# touch-tara-h.net
KiCad netlist of a schematic drawn in Altium Designer
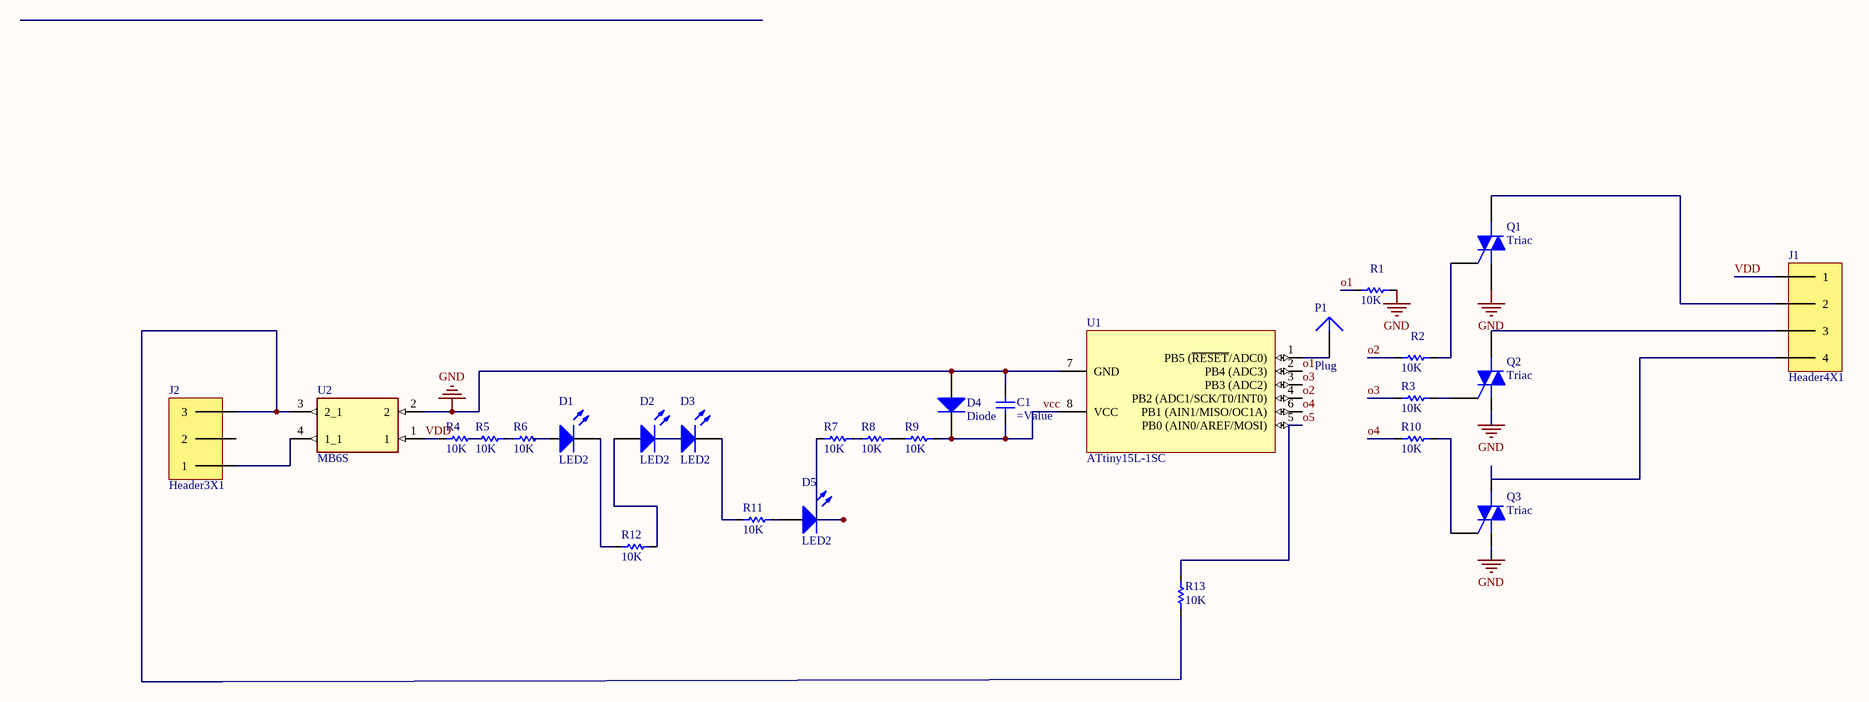
[diagram p0: touch-tara-h.SchDoc]

(export (version "E")
  (design (tool "Eeschema 10.0.6"))
  (components
    (comp (ref "C1")
      (value "~")
      (footprint "CAP 1206")
      (description "Capacitor")
      (libsource (lib "AltiumLib1") (part "Capacitor"))
    )
    (comp (ref "D1")
      (value "LED2")
      (footprint "3.2X1.6X1.1")
      (description "Typical RED, GREEN, YELLOW, AMBER GaAs LED")
      (fields (field (name "PUBLISHER") "Altium Limited"))
      (libsource (lib "Miscellaneous Devices") (part "LED2"))
    )
    (comp (ref "D2")
      (value "LED2")
      (footprint "3.2X1.6X1.1")
      (description "Typical RED, GREEN, YELLOW, AMBER GaAs LED")
      (fields (field (name "PUBLISHER") "Altium Limited"))
      (libsource (lib "Miscellaneous Devices") (part "LED2"))
    )
    (comp (ref "D3")
      (value "LED2")
      (footprint "3.2X1.6X1.1")
      (description "Typical RED, GREEN, YELLOW, AMBER GaAs LED")
      (fields (field (name "PUBLISHER") "Altium Limited"))
      (libsource (lib "Miscellaneous Devices") (part "LED2"))
    )
    (comp (ref "D4")
      (value "Diode")
      (footprint "C1206")
      (description "Default Diode")
      (fields (field (name "PUBLISHER") "Altium Limited"))
      (libsource (lib "Miscellaneous Devices") (part "Diode"))
    )
    (comp (ref "D5")
      (value "LED2")
      (footprint "3.2X1.6X1.1")
      (description "Typical RED, GREEN, YELLOW, AMBER GaAs LED")
      (fields (field (name "PUBLISHER") "Altium Limited"))
      (libsource (lib "Miscellaneous Devices") (part "LED2"))
    )
    (comp (ref "J1")
      (value "Header4X1")
      (footprint "HEADER 4X1")
      (libsource (lib "AltiumLib1") (part "Header4X1"))
    )
    (comp (ref "J2")
      (value "Header3X1")
      (footprint "HEADER 3X1")
      (libsource (lib "AltiumLib1") (part "Header3X1"))
    )
    (comp (ref "P1")
      (value "Plug")
      (footprint "PIN1")
      (fields (field (name "PUBLISHER") "Altium Limited"))
      (libsource (lib "Miscellaneous Connectors") (part "Plug"))
    )
    (comp (ref "Q1")
      (value "Triac")
      (footprint "SOT89N")
      (description "Silicon Bidirectional Triode Thyristor")
      (fields (field (name "PUBLISHER") "Altium Limited"))
      (libsource (lib "Miscellaneous Devices") (part "Triac"))
    )
    (comp (ref "Q2")
      (value "Triac")
      (footprint "SOT89N")
      (description "Silicon Bidirectional Triode Thyristor")
      (fields (field (name "PUBLISHER") "Altium Limited"))
      (libsource (lib "Miscellaneous Devices") (part "Triac"))
    )
    (comp (ref "Q3")
      (value "Triac")
      (footprint "SOT89N")
      (description "Silicon Bidirectional Triode Thyristor")
      (fields (field (name "PUBLISHER") "Altium Limited"))
      (libsource (lib "Miscellaneous Devices") (part "Triac"))
    )
    (comp (ref "R1")
      (value "10K")
      (footprint "RES 1206 (3216X08L)")
      (description "Resistor")
      (fields (field (name "TOLERANCE") "5%") (field (name "POWER") "1/4 W"))
      (libsource (lib "AltiumLib1") (part "Resistor"))
    )
    (comp (ref "R2")
      (value "10K")
      (footprint "RES 1206 (3216X08L)")
      (description "Resistor")
      (fields (field (name "TOLERANCE") "5%") (field (name "POWER") "1/4 W"))
      (libsource (lib "AltiumLib1") (part "Resistor"))
    )
    (comp (ref "R3")
      (value "10K")
      (footprint "RES 1206 (3216X08L)")
      (description "Resistor")
      (fields (field (name "TOLERANCE") "5%") (field (name "POWER") "1/4 W"))
      (libsource (lib "AltiumLib1") (part "Resistor"))
    )
    (comp (ref "R4")
      (value "10K")
      (footprint "RES 2010 (5026X08L)")
      (description "Resistor")
      (fields (field (name "TOLERANCE") "5%") (field (name "POWER") "1/4 W"))
      (libsource (lib "AltiumLib1") (part "Resistor"))
    )
    (comp (ref "R5")
      (value "10K")
      (footprint "RES 2010 (5026X08L)")
      (description "Resistor")
      (fields (field (name "TOLERANCE") "5%") (field (name "POWER") "1/4 W"))
      (libsource (lib "AltiumLib1") (part "Resistor"))
    )
    (comp (ref "R6")
      (value "10K")
      (footprint "RES 2010 (5026X08L)")
      (description "Resistor")
      (fields (field (name "TOLERANCE") "5%") (field (name "POWER") "1/4 W"))
      (libsource (lib "AltiumLib1") (part "Resistor"))
    )
    (comp (ref "R7")
      (value "10K")
      (footprint "RES 2010 (5026X08L)")
      (description "Resistor")
      (fields (field (name "TOLERANCE") "5%") (field (name "POWER") "1/4 W"))
      (libsource (lib "AltiumLib1") (part "Resistor"))
    )
    (comp (ref "R8")
      (value "10K")
      (footprint "RES 2010 (5026X08L)")
      (description "Resistor")
      (fields (field (name "TOLERANCE") "5%") (field (name "POWER") "1/4 W"))
      (libsource (lib "AltiumLib1") (part "Resistor"))
    )
    (comp (ref "R9")
      (value "10K")
      (footprint "RES 2010 (5026X08L)")
      (description "Resistor")
      (fields (field (name "TOLERANCE") "5%") (field (name "POWER") "1/4 W"))
      (libsource (lib "AltiumLib1") (part "Resistor"))
    )
    (comp (ref "R10")
      (value "10K")
      (footprint "RES 1206 (3216X08L)")
      (description "Resistor")
      (fields (field (name "TOLERANCE") "5%") (field (name "POWER") "1/4 W"))
      (libsource (lib "AltiumLib1") (part "Resistor"))
    )
    (comp (ref "R11")
      (value "10K")
      (footprint "RES 2010 (5026X08L)")
      (description "Resistor")
      (fields (field (name "TOLERANCE") "5%") (field (name "POWER") "1/4 W"))
      (libsource (lib "AltiumLib1") (part "Resistor"))
    )
    (comp (ref "R12")
      (value "10K")
      (footprint "RES 2010 (5026X08L)")
      (description "Resistor")
      (fields (field (name "TOLERANCE") "5%") (field (name "POWER") "1/4 W"))
      (libsource (lib "AltiumLib1") (part "Resistor"))
    )
    (comp (ref "R13")
      (value "10K")
      (footprint "RES 1206 (3216X08L)")
      (description "Resistor")
      (fields (field (name "TOLERANCE") "5%") (field (name "POWER") "1/4 W"))
      (libsource (lib "AltiumLib1") (part "Resistor"))
    )
    (comp (ref "U1")
      (value "ATtiny15L-1SC")
      (footprint "8S2_N")
      (description "8-Bit AVR Microcontroller with 1K Byte of Flash Memory")
      (fields (field (name "PUBLISHER") "Altium Limited"))
      (libsource (lib "Atmel Microcontroller 8-Bit AVR") (part "ATtiny15L-1SC"))
    )
    (comp (ref "U2")
      (value "MB6S")
      (footprint "SOIC245P670X270-4N")
      (description "Bridge Rectifier Single Phase Standard 600V Surface Mount 4-SOIC")
      (fields (field (name "MF") "ON Semiconductor") (field (name "DIGI-KEY_PART_NUMBER") "MB6SCT-ND"))
      (libsource (lib "MB6S") (part "MB6S"))
    )
  )
  (nets
    (net (code "1") (name "/VDD") (class "Default")
      (node (ref "J1") (pin "1") (pinfunction "1_1") (pintype "passive"))
      (node (ref "R4") (pin "1") (pinfunction "1_1") (pintype "passive"))
      (node (ref "U2") (pin "1") (pinfunction "1_1") (pintype "input"))
    )
    (net (code "2") (name "/o1") (class "Default")
      (node (ref "R1") (pin "1") (pinfunction "1_1") (pintype "passive"))
      (node (ref "U1") (pin "2") (pinfunction "PB4_(ADC3)_2") (pintype "bidirectional"))
    )
    (net (code "3") (name "/o2") (class "Default")
      (node (ref "R2") (pin "1") (pinfunction "1_1") (pintype "passive"))
      (node (ref "U1") (pin "4") (pinfunction "PB2_(ADC1/SCK/T0/INT0)_4") (pintype "bidirectional"))
    )
    (net (code "4") (name "/o3") (class "Default")
      (node (ref "R3") (pin "1") (pinfunction "1_1") (pintype "passive"))
      (node (ref "U1") (pin "3") (pinfunction "PB3_(ADC2)_3") (pintype "bidirectional"))
    )
    (net (code "5") (name "/o4") (class "Default")
      (node (ref "R10") (pin "1") (pinfunction "1_1") (pintype "passive"))
      (node (ref "U1") (pin "6") (pinfunction "PB1_(AIN1/MISO/OC1A)_6") (pintype "bidirectional"))
    )
    (net (code "6") (name "/o5") (class "Default")
      (node (ref "R13") (pin "2") (pinfunction "2_2") (pintype "passive"))
      (node (ref "U1") (pin "5") (pinfunction "PB0_(AIN0/AREF/MOSI)_5") (pintype "bidirectional"))
    )
    (net (code "7") (name "/vcc") (class "Default")
      (node (ref "C1") (pin "1") (pinfunction "+_1") (pintype "passive"))
      (node (ref "D4") (pin "2") (pinfunction "K_2") (pintype "passive"))
      (node (ref "R9") (pin "2") (pinfunction "2_2") (pintype "passive"))
      (node (ref "U1") (pin "8") (pinfunction "VCC_8") (pintype "power_in"))
    )
    (net (code "8") (name "GND") (class "Default")
      (node (ref "C1") (pin "2") (pinfunction "-_2") (pintype "passive"))
      (node (ref "D4") (pin "1") (pinfunction "A_1") (pintype "passive"))
      (node (ref "Q1") (pin "1") (pinfunction "M1_1") (pintype "passive"))
      (node (ref "Q2") (pin "1") (pinfunction "M1_1") (pintype "passive"))
      (node (ref "Q3") (pin "1") (pinfunction "M1_1") (pintype "passive"))
      (node (ref "R1") (pin "2") (pinfunction "2_2") (pintype "passive"))
      (node (ref "U1") (pin "7") (pinfunction "GND_7") (pintype "power_in"))
      (node (ref "U2") (pin "2") (pinfunction "2_2") (pintype "input"))
    )
    (net (code "9") (name "Net-(D1-A)") (class "Default")
      (node (ref "D1") (pin "1") (pinfunction "A_1") (pintype "passive"))
      (node (ref "R6") (pin "2") (pinfunction "2_2") (pintype "passive"))
    )
    (net (code "10") (name "Net-(D1-K)") (class "Default")
      (node (ref "D1") (pin "2") (pinfunction "K_2") (pintype "passive"))
      (node (ref "R12") (pin "1") (pinfunction "1_1") (pintype "passive"))
    )
    (net (code "11") (name "Net-(D2-A)") (class "Default")
      (node (ref "D2") (pin "1") (pinfunction "A_1") (pintype "passive"))
      (node (ref "R12") (pin "2") (pinfunction "2_2") (pintype "passive"))
    )
    (net (code "12") (name "Net-(D2-K)") (class "Default")
      (node (ref "D2") (pin "2") (pinfunction "K_2") (pintype "passive"))
      (node (ref "D3") (pin "1") (pinfunction "A_1") (pintype "passive"))
    )
    (net (code "13") (name "Net-(D3-K)") (class "Default")
      (node (ref "D3") (pin "2") (pinfunction "K_2") (pintype "passive"))
      (node (ref "R11") (pin "1") (pinfunction "1_1") (pintype "passive"))
    )
    (net (code "14") (name "Net-(D5-A)") (class "Default")
      (node (ref "D5") (pin "1") (pinfunction "A_1") (pintype "passive"))
      (node (ref "R11") (pin "2") (pinfunction "2_2") (pintype "passive"))
    )
    (net (code "15") (name "Net-(D5-K)") (class "Default")
      (node (ref "D5") (pin "2") (pinfunction "K_2") (pintype "passive"))
      (node (ref "R7") (pin "1") (pinfunction "1_1") (pintype "passive"))
    )
    (net (code "16") (name "Net-(Q1-G)") (class "Default")
      (node (ref "Q1") (pin "3") (pinfunction "G_3") (pintype "passive"))
      (node (ref "R2") (pin "2") (pinfunction "2_2") (pintype "passive"))
    )
    (net (code "17") (name "Net-(Q1-M2)") (class "Default")
      (node (ref "J1") (pin "2") (pinfunction "2_2") (pintype "passive"))
      (node (ref "Q1") (pin "2") (pinfunction "M2_2") (pintype "passive"))
    )
    (net (code "18") (name "Net-(Q2-G)") (class "Default")
      (node (ref "Q2") (pin "3") (pinfunction "G_3") (pintype "passive"))
      (node (ref "R3") (pin "2") (pinfunction "2_2") (pintype "passive"))
    )
    (net (code "19") (name "Net-(Q2-M2)") (class "Default")
      (node (ref "J1") (pin "3") (pinfunction "3_3") (pintype "passive"))
      (node (ref "Q2") (pin "2") (pinfunction "M2_2") (pintype "passive"))
    )
    (net (code "20") (name "Net-(Q3-G)") (class "Default")
      (node (ref "Q3") (pin "3") (pinfunction "G_3") (pintype "passive"))
      (node (ref "R10") (pin "2") (pinfunction "2_2") (pintype "passive"))
    )
    (net (code "21") (name "Net-(Q3-M2)") (class "Default")
      (node (ref "J1") (pin "4") (pinfunction "4_4") (pintype "passive"))
      (node (ref "Q3") (pin "2") (pinfunction "M2_2") (pintype "passive"))
    )
    (net (code "22") (name "Net-(R4-Pad2)") (class "Default")
      (node (ref "R4") (pin "2") (pinfunction "2_2") (pintype "passive"))
      (node (ref "R5") (pin "1") (pinfunction "1_1") (pintype "passive"))
    )
    (net (code "23") (name "Net-(R5-Pad2)") (class "Default")
      (node (ref "R5") (pin "2") (pinfunction "2_2") (pintype "passive"))
      (node (ref "R6") (pin "1") (pinfunction "1_1") (pintype "passive"))
    )
    (net (code "24") (name "Net-(R7-Pad2)") (class "Default")
      (node (ref "R7") (pin "2") (pinfunction "2_2") (pintype "passive"))
      (node (ref "R8") (pin "1") (pinfunction "1_1") (pintype "passive"))
    )
    (net (code "25") (name "Net-(R8-Pad2)") (class "Default")
      (node (ref "R8") (pin "2") (pinfunction "2_2") (pintype "passive"))
      (node (ref "R9") (pin "1") (pinfunction "1_1") (pintype "passive"))
    )
    (net (code "26") (name "Net-(U1-PB5_(~{RESET}{slash}ADC0))") (class "Default")
      (node (ref "P1") (pin "1") (pinfunction "1_1") (pintype "passive"))
      (node (ref "U1") (pin "1") (pinfunction "PB5_(~{RESET}/ADC0)_1") (pintype "bidirectional"))
    )
    (net (code "27") (name "Net-(U2-1_1)") (class "Default")
      (node (ref "J2") (pin "1") (pinfunction "1_1") (pintype "passive"))
      (node (ref "U2") (pin "4") (pinfunction "1_1_4") (pintype "output"))
    )
    (net (code "28") (name "Net-(U2-2_1)") (class "Default")
      (node (ref "J2") (pin "3") (pinfunction "3_3") (pintype "passive"))
      (node (ref "R13") (pin "1") (pinfunction "1_1") (pintype "passive"))
      (node (ref "U2") (pin "3") (pinfunction "2_1_3") (pintype "output"))
    )
    (net (code "29") (name "unconnected-(J2-Pad2)") (class "Default")
      (node (ref "J2") (pin "2") (pinfunction "2_2") (pintype "passive"))
    )
  )
)
